# SCH_NFC-Business-Tag_2024-04-17.net
KiCad netlist of a schematic drawn in EasyEDA
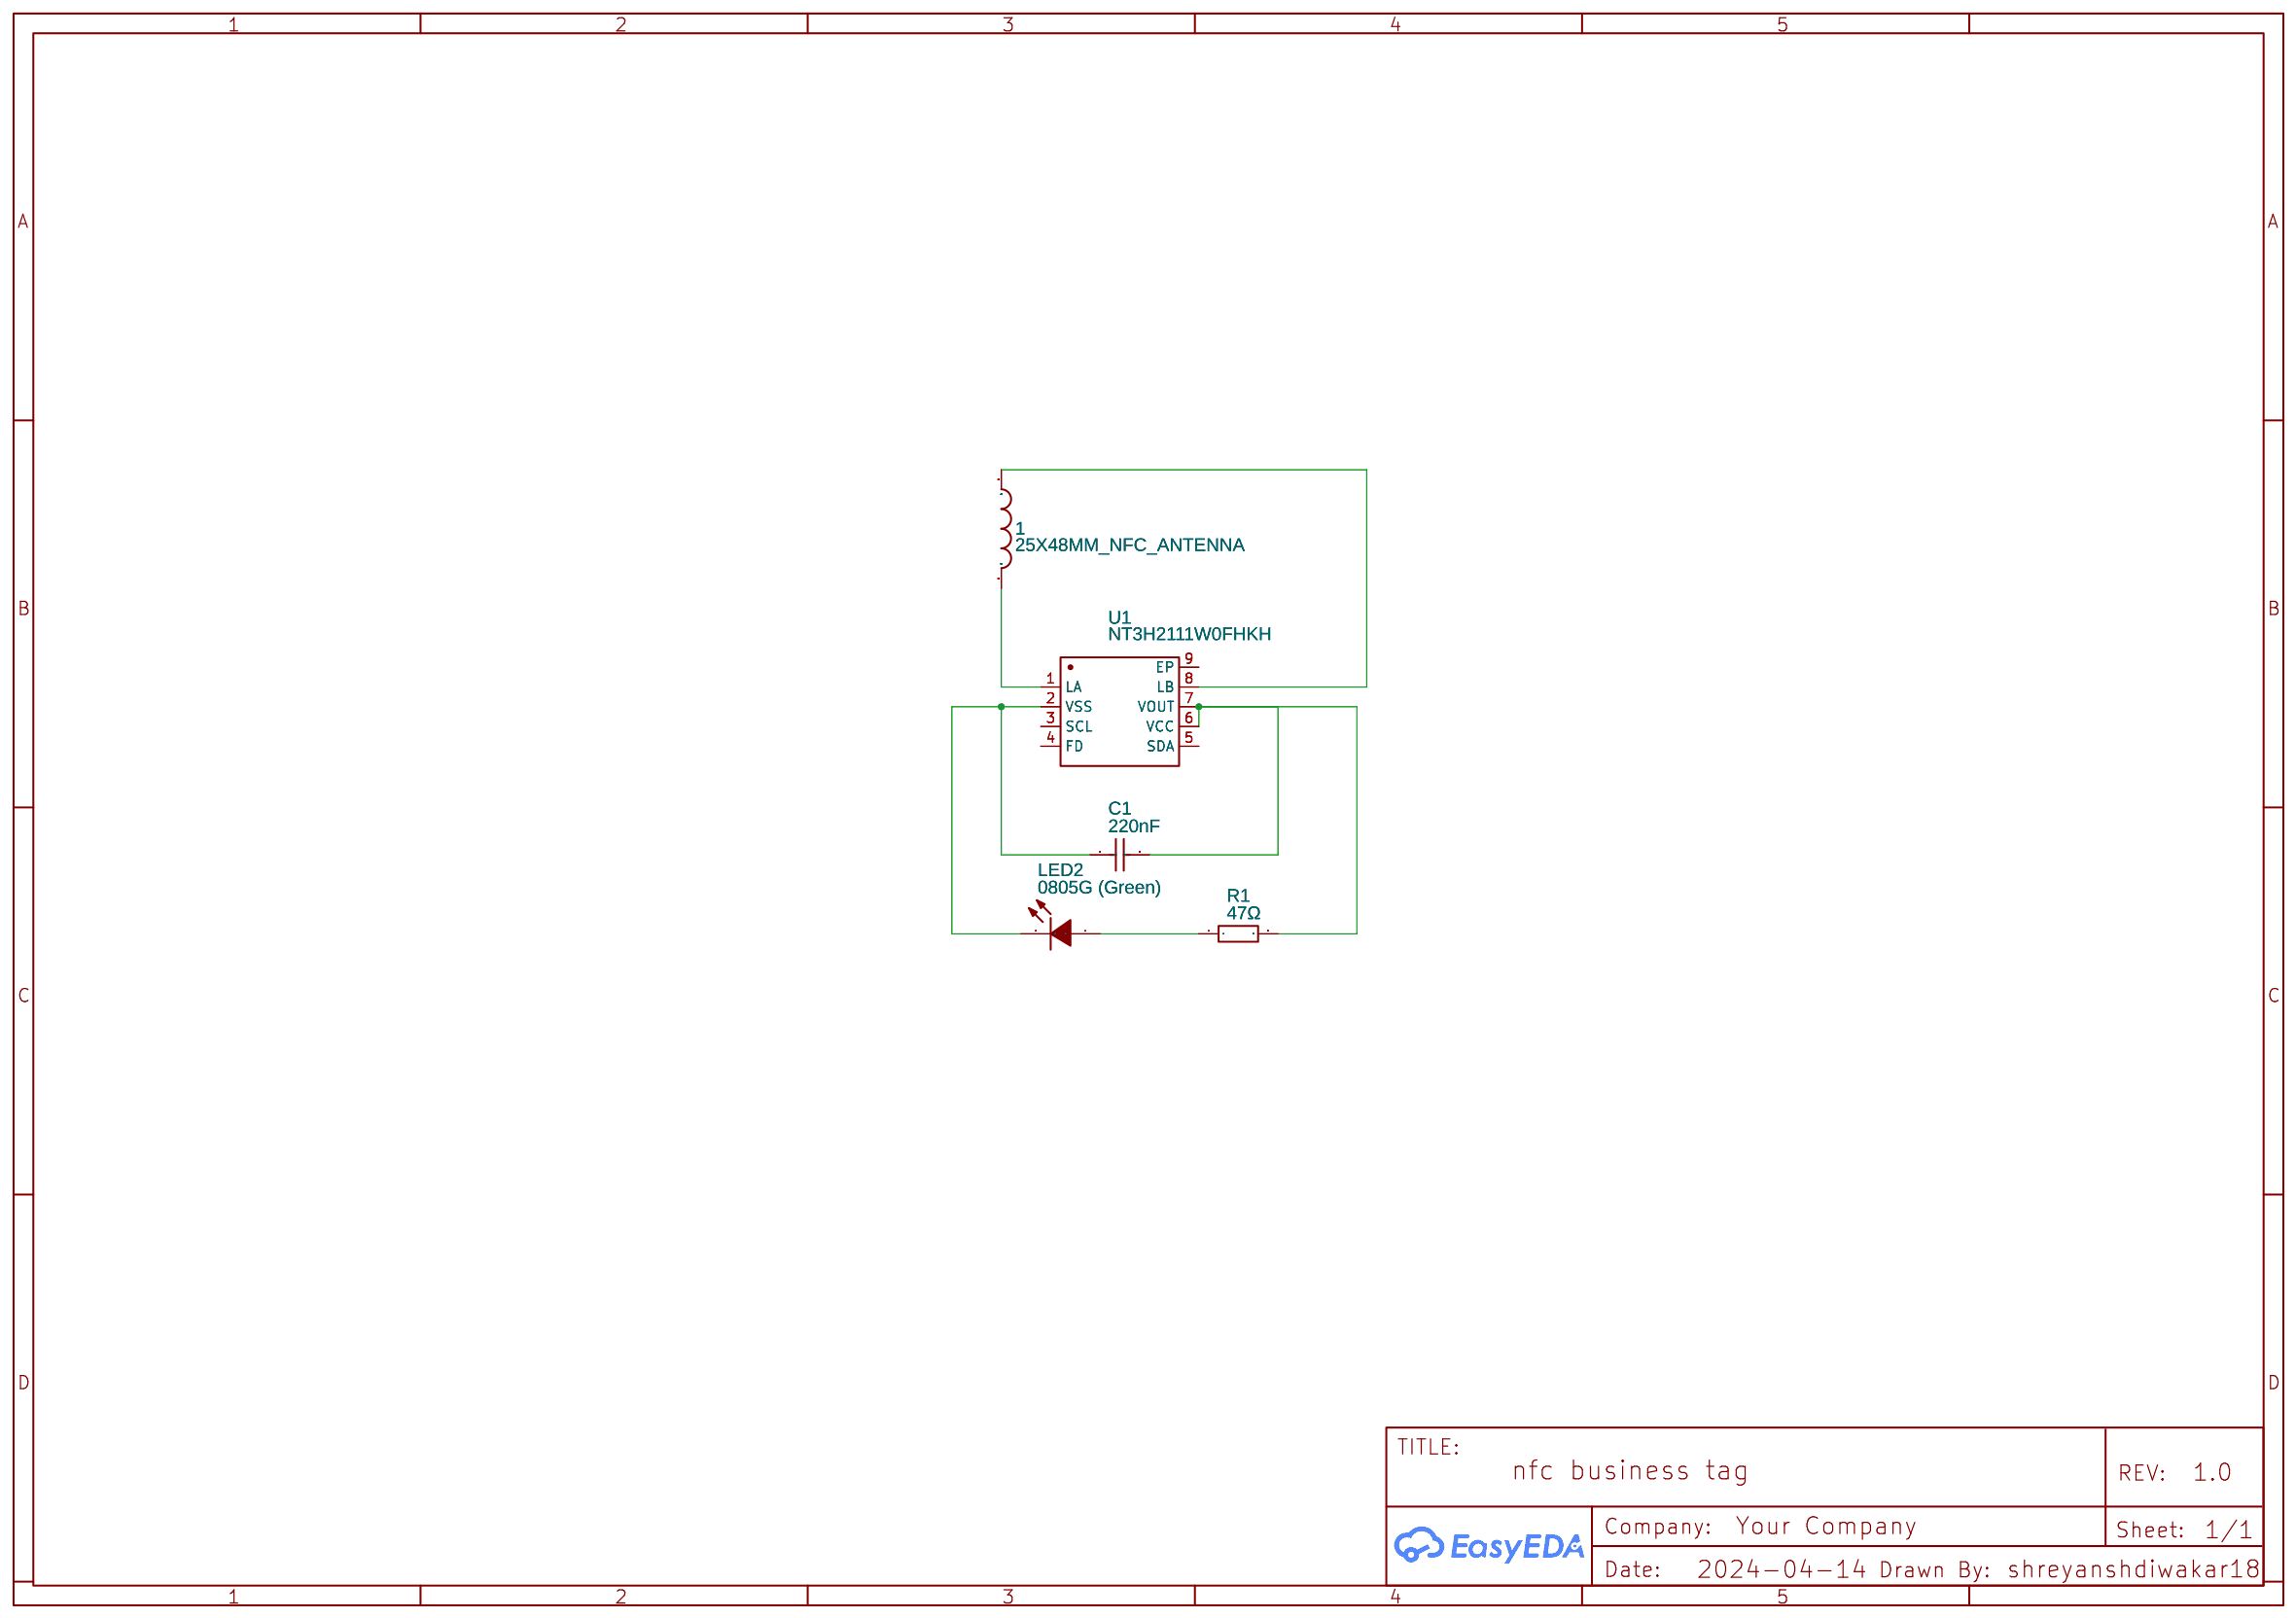
[diagram p0: schematic sheet]

(export (version "E")
  (design (tool "Eeschema 10.0.6"))
  (components
    (comp (ref "1") (value "25X48MM_NFC_ANTENNA") (libsource (lib "") (part "25X48MM_NFC_ANTENNA")))
    (comp (ref "C1")
      (value "220nF")
      (fields
        (field (name "Manufacturer Part") "CL10B224KA8NNNC")
        (field (name "Manufacturer") "SAMSUNG(三星)")
      )
      (libsource (lib "") (part "CL10B224KA8NNNC"))
    )
    (comp (ref "LED2")
      (value "0805G (Green)")
      (fields (field (name "Manufacturer Part") "KT-0805G") (field (name "Manufacturer") "KENTO"))
      (libsource (lib "") (part "0805G (Green)"))
    )
    (comp (ref "R1")
      (value "47Ω")
      (fields
        (field (name "Manufacturer Part") "0603WAF470JT5E")
        (field (name "Manufacturer") "UNI-ROYAL(厚声)")
      )
      (libsource (lib "") (part "0603WAF470JT5E"))
    )
    (comp (ref "U1")
      (value "NT3H2111W0FHKH")
      (fields (field (name "Manufacturer") "NXP(恩智浦)"))
      (libsource (lib "") (part "NT3H2111W0FHKH"))
    )
  )
  (nets
    (net (code "1") (name "Net-(LED2-A)") (class "Default")
      (node (ref "LED2") (pin "1") (pinfunction "A_1") (pintype "unspecified"))
      (node (ref "R1") (pin "1") (pinfunction "1_1") (pintype "input"))
    )
    (net (code "2") (name "Net-(LED2-K)") (class "Default")
      (node (ref "C1") (pin "1") (pinfunction "1_1") (pintype "input"))
      (node (ref "LED2") (pin "2") (pinfunction "K_2") (pintype "unspecified"))
      (node (ref "U1") (pin "2") (pinfunction "VSS_2") (pintype "unspecified"))
    )
    (net (code "3") (name "Net-(U1-LA)") (class "Default")
      (node (ref "1") (pin "P$2") (pinfunction "P$2_P$2") (pintype "bidirectional"))
      (node (ref "U1") (pin "1") (pinfunction "LA_1") (pintype "unspecified"))
    )
    (net (code "4") (name "Net-(U1-LB)") (class "Default")
      (node (ref "1") (pin "P$1") (pinfunction "P$1_P$1") (pintype "bidirectional"))
      (node (ref "U1") (pin "8") (pinfunction "LB_8") (pintype "unspecified"))
    )
    (net (code "5") (name "Net-(U1-VCC)") (class "Default")
      (node (ref "C1") (pin "2") (pinfunction "2_2") (pintype "input"))
      (node (ref "R1") (pin "2") (pinfunction "2_2") (pintype "input"))
      (node (ref "U1") (pin "6") (pinfunction "VCC_6") (pintype "unspecified"))
      (node (ref "U1") (pin "7") (pinfunction "VOUT_7") (pintype "unspecified"))
    )
    (net (code "6") (name "unconnected-(U1-EP-Pad9)") (class "Default")
      (node (ref "U1") (pin "9") (pinfunction "EP_9") (pintype "unspecified"))
    )
    (net (code "7") (name "unconnected-(U1-FD-Pad4)") (class "Default")
      (node (ref "U1") (pin "4") (pinfunction "FD_4") (pintype "unspecified"))
    )
    (net (code "8") (name "unconnected-(U1-SCL-Pad3)") (class "Default")
      (node (ref "U1") (pin "3") (pinfunction "SCL_3") (pintype "unspecified"))
    )
    (net (code "9") (name "unconnected-(U1-SDA-Pad5)") (class "Default")
      (node (ref "U1") (pin "5") (pinfunction "SDA_5") (pintype "unspecified"))
    )
  )
)
